# S7CAS-PLEIADES-CARTE-MERE_P07_FPGA_3.net
KiCad netlist of a schematic drawn in Altium Designer
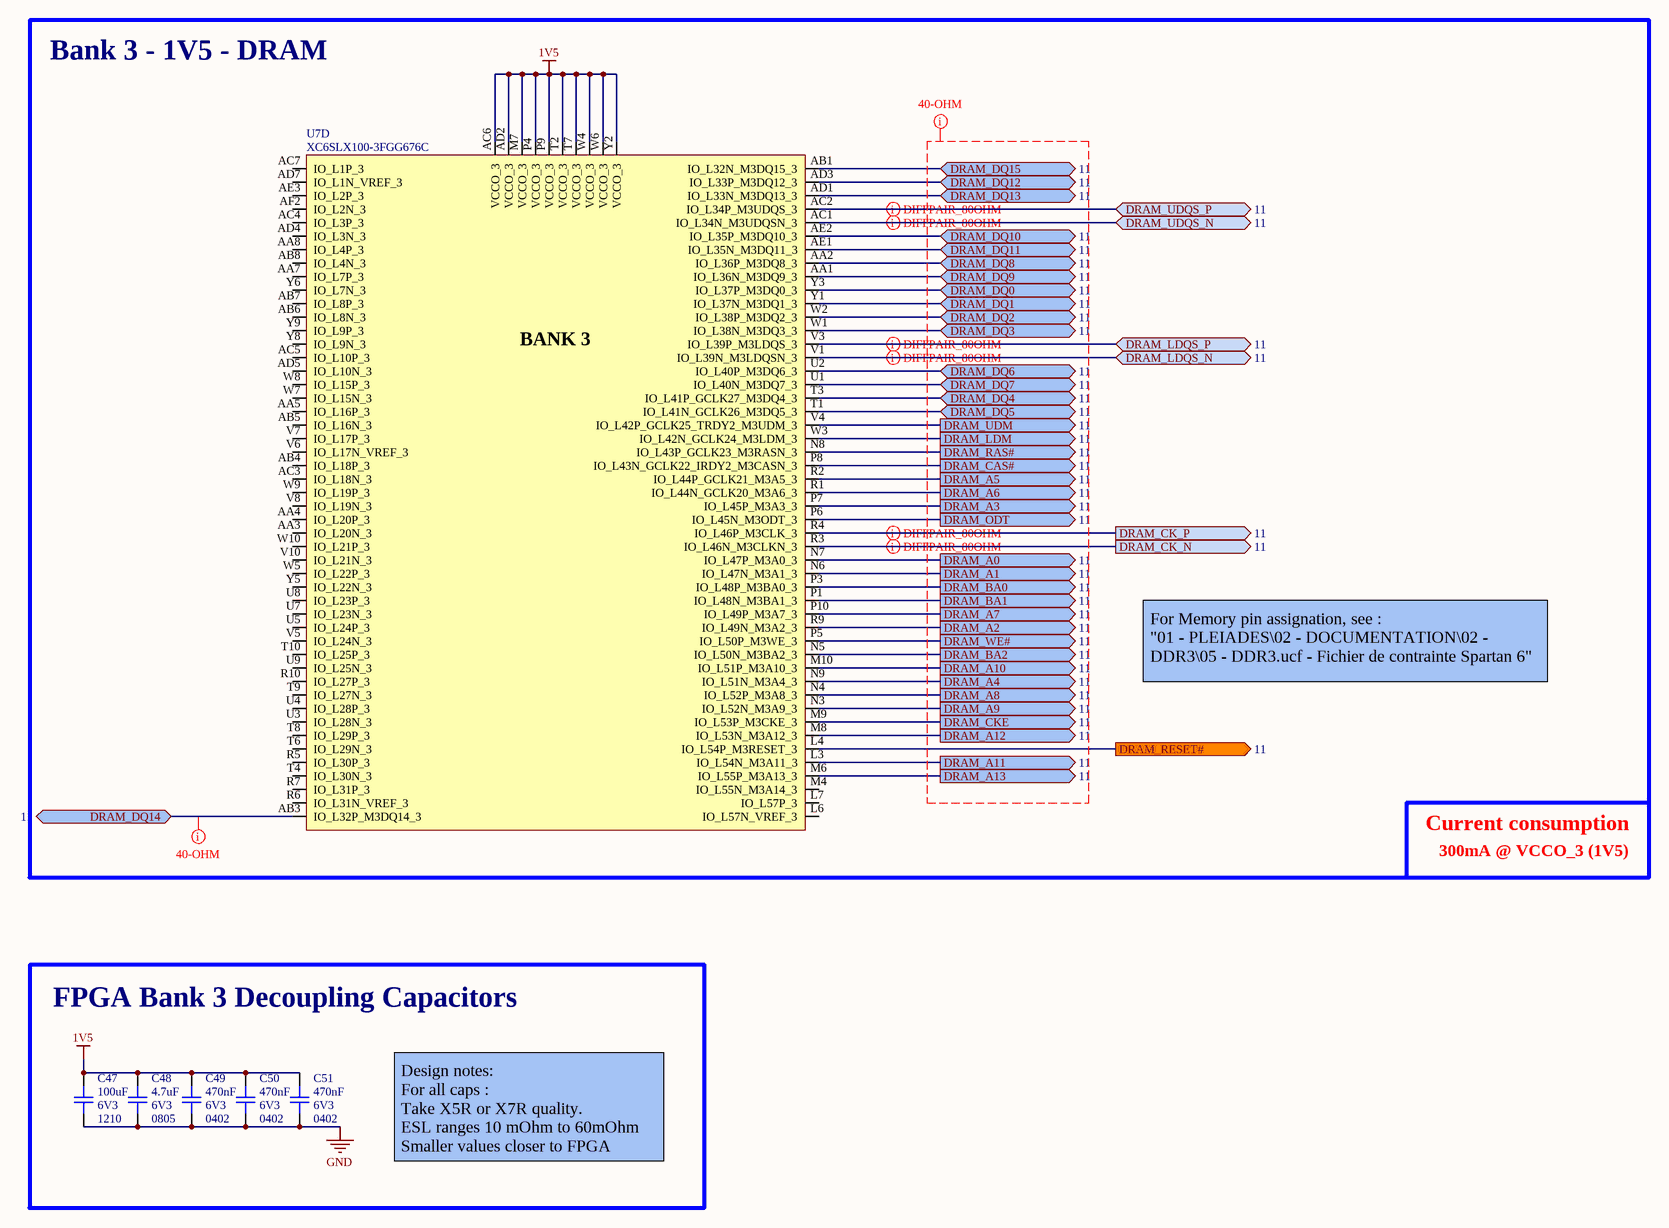
[diagram p0: S7CAS-PLEIADES-CARTE-MERE_P07_FPGA_3.SchDoc]

(export (version "E")
  (design (tool "Eeschema 10.0.6"))
  (components
    (comp (ref "C47")
      (value "100uF")
      (footprint "CAP_1210")
      (description "CAP - 1210")
      (fields
        (field (name "VOLTAGE") "6V3")
        (field (name "PACKAGE") "1210")
        (field (name "CREATEDBY") "Jonathan Bouchard")
      )
      (libsource (lib "S7CAS_LIB2021") (part "CAP - 1210"))
    )
    (comp (ref "C48")
      (value "4.7uF")
      (footprint "CAP_0805")
      (description "CAP - 0805")
      (fields
        (field (name "VOLTAGE") "6V3")
        (field (name "PACKAGE") "0805")
        (field (name "CREATEDBY") "Jonathan Bouchard")
      )
      (libsource (lib "S7CAS_LIB2021") (part "CAP - 0805"))
    )
    (comp (ref "C49")
      (value "470nF")
      (footprint "CAP_0402")
      (description "CAP - 0402")
      (fields
        (field (name "VOLTAGE") "6V3")
        (field (name "PACKAGE") "0402")
        (field (name "CREATEDBY") "Jonathan Bouchard")
      )
      (libsource (lib "S7CAS_LIB2021") (part "CAP - 0402"))
    )
    (comp (ref "C50")
      (value "470nF")
      (footprint "CAP_0402")
      (description "CAP - 0402")
      (fields
        (field (name "VOLTAGE") "6V3")
        (field (name "PACKAGE") "0402")
        (field (name "CREATEDBY") "Jonathan Bouchard")
      )
      (libsource (lib "S7CAS_LIB2021") (part "CAP - 0402"))
    )
    (comp (ref "C51")
      (value "470nF")
      (footprint "CAP_0402")
      (description "CAP - 0402")
      (fields
        (field (name "VOLTAGE") "6V3")
        (field (name "PACKAGE") "0402")
        (field (name "CREATEDBY") "Jonathan Bouchard")
      )
      (libsource (lib "S7CAS_LIB2021") (part "CAP - 0402"))
    )
    (comp (ref "U7")
      (value "XC6SLX100-3FGG676C")
      (footprint "FPGA_XILINX_FGG676")
      (description "FPGA - XILINX SPARTAN 6 480 I/O - BGA-676")
      (fields
        (field (name "VOLTAGE") "1.14 V ~ 1.26 V")
        (field (name "MFG") "Xilinx")
        (field (name "CREATEDBY") "Jonathan Bouchard")
      )
      (libsource (lib "S7CAS_LIB2021") (part "FPGA_XC6SLX100-3FGG676C"))
    )
  )
  (nets
    (net (code "1") (name "/DRAM_A0") (class "Default")
      (node (ref "U7") (pin "N7") (pinfunction "IO_L47P_M3A0_3_N7") (pintype "passive"))
    )
    (net (code "2") (name "/DRAM_A1") (class "Default")
      (node (ref "U7") (pin "N6") (pinfunction "IO_L47N_M3A1_3_N6") (pintype "passive"))
    )
    (net (code "3") (name "/DRAM_A2") (class "Default")
      (node (ref "U7") (pin "R9") (pinfunction "IO_L49N_M3A2_3_R9") (pintype "passive"))
    )
    (net (code "4") (name "/DRAM_A3") (class "Default")
      (node (ref "U7") (pin "P7") (pinfunction "IO_L45P_M3A3_3_P7") (pintype "passive"))
    )
    (net (code "5") (name "/DRAM_A4") (class "Default")
      (node (ref "U7") (pin "N9") (pinfunction "IO_L51N_M3A4_3_N9") (pintype "passive"))
    )
    (net (code "6") (name "/DRAM_A5") (class "Default")
      (node (ref "U7") (pin "R2") (pinfunction "IO_L44P_GCLK21_M3A5_3_R2") (pintype "passive"))
    )
    (net (code "7") (name "/DRAM_A6") (class "Default")
      (node (ref "U7") (pin "R1") (pinfunction "IO_L44N_GCLK20_M3A6_3_R1") (pintype "passive"))
    )
    (net (code "8") (name "/DRAM_A7") (class "Default")
      (node (ref "U7") (pin "P10") (pinfunction "IO_L49P_M3A7_3_P10") (pintype "passive"))
    )
    (net (code "9") (name "/DRAM_A8") (class "Default")
      (node (ref "U7") (pin "N4") (pinfunction "IO_L52P_M3A8_3_N4") (pintype "passive"))
    )
    (net (code "10") (name "/DRAM_A9") (class "Default")
      (node (ref "U7") (pin "N3") (pinfunction "IO_L52N_M3A9_3_N3") (pintype "passive"))
    )
    (net (code "11") (name "/DRAM_A10") (class "Default")
      (node (ref "U7") (pin "M10") (pinfunction "IO_L51P_M3A10_3_M10") (pintype "passive"))
    )
    (net (code "12") (name "/DRAM_A11") (class "Default")
      (node (ref "U7") (pin "L3") (pinfunction "IO_L54N_M3A11_3_L3") (pintype "passive"))
    )
    (net (code "13") (name "/DRAM_A12") (class "Default")
      (node (ref "U7") (pin "M8") (pinfunction "IO_L53N_M3A12_3_M8") (pintype "passive"))
    )
    (net (code "14") (name "/DRAM_A13") (class "Default")
      (node (ref "U7") (pin "M6") (pinfunction "IO_L55P_M3A13_3_M6") (pintype "passive"))
    )
    (net (code "15") (name "/DRAM_BA0") (class "Default")
      (node (ref "U7") (pin "P3") (pinfunction "IO_L48P_M3BA0_3_P3") (pintype "passive"))
    )
    (net (code "16") (name "/DRAM_BA1") (class "Default")
      (node (ref "U7") (pin "P1") (pinfunction "IO_L48N_M3BA1_3_P1") (pintype "passive"))
    )
    (net (code "17") (name "/DRAM_BA2") (class "Default")
      (node (ref "U7") (pin "N5") (pinfunction "IO_L50N_M3BA2_3_N5") (pintype "passive"))
    )
    (net (code "18") (name "/DRAM_CAS#") (class "Default")
      (node (ref "U7") (pin "P8") (pinfunction "IO_L43N_GCLK22_IRDY2_M3CASN_3_P8") (pintype "passive"))
    )
    (net (code "19") (name "/DRAM_CKE") (class "Default")
      (node (ref "U7") (pin "M9") (pinfunction "IO_L53P_M3CKE_3_M9") (pintype "passive"))
    )
    (net (code "20") (name "/DRAM_CK_N") (class "Default")
      (node (ref "U7") (pin "R3") (pinfunction "IO_L46N_M3CLKN_3_R3") (pintype "passive"))
    )
    (net (code "21") (name "/DRAM_CK_P") (class "Default")
      (node (ref "U7") (pin "R4") (pinfunction "IO_L46P_M3CLK_3_R4") (pintype "passive"))
    )
    (net (code "22") (name "/DRAM_DQ0") (class "Default")
      (node (ref "U7") (pin "Y3") (pinfunction "IO_L37P_M3DQ0_3_Y3") (pintype "passive"))
    )
    (net (code "23") (name "/DRAM_DQ1") (class "Default")
      (node (ref "U7") (pin "Y1") (pinfunction "IO_L37N_M3DQ1_3_Y1") (pintype "passive"))
    )
    (net (code "24") (name "/DRAM_DQ2") (class "Default")
      (node (ref "U7") (pin "W2") (pinfunction "IO_L38P_M3DQ2_3_W2") (pintype "passive"))
    )
    (net (code "25") (name "/DRAM_DQ3") (class "Default")
      (node (ref "U7") (pin "W1") (pinfunction "IO_L38N_M3DQ3_3_W1") (pintype "passive"))
    )
    (net (code "26") (name "/DRAM_DQ4") (class "Default")
      (node (ref "U7") (pin "T3") (pinfunction "IO_L41P_GCLK27_M3DQ4_3_T3") (pintype "passive"))
    )
    (net (code "27") (name "/DRAM_DQ5") (class "Default")
      (node (ref "U7") (pin "T1") (pinfunction "IO_L41N_GCLK26_M3DQ5_3_T1") (pintype "passive"))
    )
    (net (code "28") (name "/DRAM_DQ6") (class "Default")
      (node (ref "U7") (pin "U2") (pinfunction "IO_L40P_M3DQ6_3_U2") (pintype "passive"))
    )
    (net (code "29") (name "/DRAM_DQ7") (class "Default")
      (node (ref "U7") (pin "U1") (pinfunction "IO_L40N_M3DQ7_3_U1") (pintype "passive"))
    )
    (net (code "30") (name "/DRAM_DQ8") (class "Default")
      (node (ref "U7") (pin "AA2") (pinfunction "IO_L36P_M3DQ8_3_AA2") (pintype "passive"))
    )
    (net (code "31") (name "/DRAM_DQ9") (class "Default")
      (node (ref "U7") (pin "AA1") (pinfunction "IO_L36N_M3DQ9_3_AA1") (pintype "passive"))
    )
    (net (code "32") (name "/DRAM_DQ10") (class "Default")
      (node (ref "U7") (pin "AE2") (pinfunction "IO_L35P_M3DQ10_3_AE2") (pintype "passive"))
    )
    (net (code "33") (name "/DRAM_DQ11") (class "Default")
      (node (ref "U7") (pin "AE1") (pinfunction "IO_L35N_M3DQ11_3_AE1") (pintype "passive"))
    )
    (net (code "34") (name "/DRAM_DQ12") (class "Default")
      (node (ref "U7") (pin "AD3") (pinfunction "IO_L33P_M3DQ12_3_AD3") (pintype "passive"))
    )
    (net (code "35") (name "/DRAM_DQ13") (class "Default")
      (node (ref "U7") (pin "AD1") (pinfunction "IO_L33N_M3DQ13_3_AD1") (pintype "passive"))
    )
    (net (code "36") (name "/DRAM_DQ14") (class "Default")
      (node (ref "U7") (pin "AB3") (pinfunction "IO_L32P_M3DQ14_3_AB3") (pintype "passive"))
    )
    (net (code "37") (name "/DRAM_DQ15") (class "Default")
      (node (ref "U7") (pin "AB1") (pinfunction "IO_L32N_M3DQ15_3_AB1") (pintype "passive"))
    )
    (net (code "38") (name "/DRAM_LDM") (class "Default")
      (node (ref "U7") (pin "W3") (pinfunction "IO_L42N_GCLK24_M3LDM_3_W3") (pintype "passive"))
    )
    (net (code "39") (name "/DRAM_LDQS_N") (class "Default")
      (node (ref "U7") (pin "V1") (pinfunction "IO_L39N_M3LDQSN_3_V1") (pintype "passive"))
    )
    (net (code "40") (name "/DRAM_LDQS_P") (class "Default")
      (node (ref "U7") (pin "V3") (pinfunction "IO_L39P_M3LDQS_3_V3") (pintype "passive"))
    )
    (net (code "41") (name "/DRAM_ODT") (class "Default")
      (node (ref "U7") (pin "P6") (pinfunction "IO_L45N_M3ODT_3_P6") (pintype "passive"))
    )
    (net (code "42") (name "/DRAM_RAS#") (class "Default")
      (node (ref "U7") (pin "N8") (pinfunction "IO_L43P_GCLK23_M3RASN_3_N8") (pintype "passive"))
    )
    (net (code "43") (name "/DRAM_RESET#") (class "Default")
      (node (ref "U7") (pin "L4") (pinfunction "IO_L54P_M3RESET_3_L4") (pintype "passive"))
    )
    (net (code "44") (name "/DRAM_UDM") (class "Default")
      (node (ref "U7") (pin "V4") (pinfunction "IO_L42P_GCLK25_TRDY2_M3UDM_3_V4") (pintype "passive"))
    )
    (net (code "45") (name "/DRAM_UDQS_N") (class "Default")
      (node (ref "U7") (pin "AC1") (pinfunction "IO_L34N_M3UDQSN_3_AC1") (pintype "passive"))
    )
    (net (code "46") (name "/DRAM_UDQS_P") (class "Default")
      (node (ref "U7") (pin "AC2") (pinfunction "IO_L34P_M3UDQS_3_AC2") (pintype "passive"))
    )
    (net (code "47") (name "/DRAM_WE#") (class "Default")
      (node (ref "U7") (pin "P5") (pinfunction "IO_L50P_M3WE_3_P5") (pintype "passive"))
    )
    (net (code "48") (name "1V5") (class "Default")
      (node (ref "C47") (pin "2") (pinfunction "2_2") (pintype "passive"))
      (node (ref "C48") (pin "2") (pinfunction "2_2") (pintype "passive"))
      (node (ref "C49") (pin "2") (pinfunction "2_2") (pintype "passive"))
      (node (ref "C50") (pin "2") (pinfunction "2_2") (pintype "passive"))
      (node (ref "C51") (pin "2") (pinfunction "2_2") (pintype "passive"))
      (node (ref "U7") (pin "AC6") (pinfunction "VCCO_3_AC6") (pintype "passive"))
      (node (ref "U7") (pin "AD2") (pinfunction "VCCO_3_AD2") (pintype "passive"))
      (node (ref "U7") (pin "M7") (pinfunction "VCCO_3_M7") (pintype "passive"))
      (node (ref "U7") (pin "P4") (pinfunction "VCCO_3_P4") (pintype "passive"))
      (node (ref "U7") (pin "P9") (pinfunction "VCCO_3_P9") (pintype "passive"))
      (node (ref "U7") (pin "T2") (pinfunction "VCCO_3_T2") (pintype "passive"))
      (node (ref "U7") (pin "T7") (pinfunction "VCCO_3_T7") (pintype "passive"))
      (node (ref "U7") (pin "W4") (pinfunction "VCCO_3_W4") (pintype "passive"))
      (node (ref "U7") (pin "W6") (pinfunction "VCCO_3_W6") (pintype "passive"))
      (node (ref "U7") (pin "Y2") (pinfunction "VCCO_3_Y2") (pintype "passive"))
    )
    (net (code "49") (name "GND") (class "Default")
      (node (ref "C47") (pin "1") (pinfunction "1_1") (pintype "passive"))
      (node (ref "C48") (pin "1") (pinfunction "1_1") (pintype "passive"))
      (node (ref "C49") (pin "1") (pinfunction "1_1") (pintype "passive"))
      (node (ref "C50") (pin "1") (pinfunction "1_1") (pintype "passive"))
      (node (ref "C51") (pin "1") (pinfunction "1_1") (pintype "passive"))
    )
    (net (code "50") (name "unconnected-(U7D-IO_L1N_VREF_3-PadAD7)") (class "Default")
      (node (ref "U7") (pin "AD7") (pinfunction "IO_L1N_VREF_3_AD7") (pintype "passive"))
    )
    (net (code "51") (name "unconnected-(U7D-IO_L1P_3-PadAC7)") (class "Default")
      (node (ref "U7") (pin "AC7") (pinfunction "IO_L1P_3_AC7") (pintype "passive"))
    )
    (net (code "52") (name "unconnected-(U7D-IO_L2N_3-PadAF2)") (class "Default")
      (node (ref "U7") (pin "AF2") (pinfunction "IO_L2N_3_AF2") (pintype "passive"))
    )
    (net (code "53") (name "unconnected-(U7D-IO_L2P_3-PadAE3)") (class "Default")
      (node (ref "U7") (pin "AE3") (pinfunction "IO_L2P_3_AE3") (pintype "passive"))
    )
    (net (code "54") (name "unconnected-(U7D-IO_L3N_3-PadAD4)") (class "Default")
      (node (ref "U7") (pin "AD4") (pinfunction "IO_L3N_3_AD4") (pintype "passive"))
    )
    (net (code "55") (name "unconnected-(U7D-IO_L3P_3-PadAC4)") (class "Default")
      (node (ref "U7") (pin "AC4") (pinfunction "IO_L3P_3_AC4") (pintype "passive"))
    )
    (net (code "56") (name "unconnected-(U7D-IO_L4N_3-PadAB8)") (class "Default")
      (node (ref "U7") (pin "AB8") (pinfunction "IO_L4N_3_AB8") (pintype "passive"))
    )
    (net (code "57") (name "unconnected-(U7D-IO_L4P_3-PadAA8)") (class "Default")
      (node (ref "U7") (pin "AA8") (pinfunction "IO_L4P_3_AA8") (pintype "passive"))
    )
    (net (code "58") (name "unconnected-(U7D-IO_L7N_3-PadY6)") (class "Default")
      (node (ref "U7") (pin "Y6") (pinfunction "IO_L7N_3_Y6") (pintype "passive"))
    )
    (net (code "59") (name "unconnected-(U7D-IO_L7P_3-PadAA7)") (class "Default")
      (node (ref "U7") (pin "AA7") (pinfunction "IO_L7P_3_AA7") (pintype "passive"))
    )
    (net (code "60") (name "unconnected-(U7D-IO_L8N_3-PadAB6)") (class "Default")
      (node (ref "U7") (pin "AB6") (pinfunction "IO_L8N_3_AB6") (pintype "passive"))
    )
    (net (code "61") (name "unconnected-(U7D-IO_L8P_3-PadAB7)") (class "Default")
      (node (ref "U7") (pin "AB7") (pinfunction "IO_L8P_3_AB7") (pintype "passive"))
    )
    (net (code "62") (name "unconnected-(U7D-IO_L9N_3-PadY8)") (class "Default")
      (node (ref "U7") (pin "Y8") (pinfunction "IO_L9N_3_Y8") (pintype "passive"))
    )
    (net (code "63") (name "unconnected-(U7D-IO_L9P_3-PadY9)") (class "Default")
      (node (ref "U7") (pin "Y9") (pinfunction "IO_L9P_3_Y9") (pintype "passive"))
    )
    (net (code "64") (name "unconnected-(U7D-IO_L10N_3-PadAD5)") (class "Default")
      (node (ref "U7") (pin "AD5") (pinfunction "IO_L10N_3_AD5") (pintype "passive"))
    )
    (net (code "65") (name "unconnected-(U7D-IO_L10P_3-PadAC5)") (class "Default")
      (node (ref "U7") (pin "AC5") (pinfunction "IO_L10P_3_AC5") (pintype "passive"))
    )
    (net (code "66") (name "unconnected-(U7D-IO_L15N_3-PadW7)") (class "Default")
      (node (ref "U7") (pin "W7") (pinfunction "IO_L15N_3_W7") (pintype "passive"))
    )
    (net (code "67") (name "unconnected-(U7D-IO_L15P_3-PadW8)") (class "Default")
      (node (ref "U7") (pin "W8") (pinfunction "IO_L15P_3_W8") (pintype "passive"))
    )
    (net (code "68") (name "unconnected-(U7D-IO_L16N_3-PadAB5)") (class "Default")
      (node (ref "U7") (pin "AB5") (pinfunction "IO_L16N_3_AB5") (pintype "passive"))
    )
    (net (code "69") (name "unconnected-(U7D-IO_L16P_3-PadAA5)") (class "Default")
      (node (ref "U7") (pin "AA5") (pinfunction "IO_L16P_3_AA5") (pintype "passive"))
    )
    (net (code "70") (name "unconnected-(U7D-IO_L17N_VREF_3-PadV6)") (class "Default")
      (node (ref "U7") (pin "V6") (pinfunction "IO_L17N_VREF_3_V6") (pintype "passive"))
    )
    (net (code "71") (name "unconnected-(U7D-IO_L17P_3-PadV7)") (class "Default")
      (node (ref "U7") (pin "V7") (pinfunction "IO_L17P_3_V7") (pintype "passive"))
    )
    (net (code "72") (name "unconnected-(U7D-IO_L18N_3-PadAC3)") (class "Default")
      (node (ref "U7") (pin "AC3") (pinfunction "IO_L18N_3_AC3") (pintype "passive"))
    )
    (net (code "73") (name "unconnected-(U7D-IO_L18P_3-PadAB4)") (class "Default")
      (node (ref "U7") (pin "AB4") (pinfunction "IO_L18P_3_AB4") (pintype "passive"))
    )
    (net (code "74") (name "unconnected-(U7D-IO_L19N_3-PadV8)") (class "Default")
      (node (ref "U7") (pin "V8") (pinfunction "IO_L19N_3_V8") (pintype "passive"))
    )
    (net (code "75") (name "unconnected-(U7D-IO_L19P_3-PadW9)") (class "Default")
      (node (ref "U7") (pin "W9") (pinfunction "IO_L19P_3_W9") (pintype "passive"))
    )
    (net (code "76") (name "unconnected-(U7D-IO_L20N_3-PadAA3)") (class "Default")
      (node (ref "U7") (pin "AA3") (pinfunction "IO_L20N_3_AA3") (pintype "passive"))
    )
    (net (code "77") (name "unconnected-(U7D-IO_L20P_3-PadAA4)") (class "Default")
      (node (ref "U7") (pin "AA4") (pinfunction "IO_L20P_3_AA4") (pintype "passive"))
    )
    (net (code "78") (name "unconnected-(U7D-IO_L21N_3-PadV10)") (class "Default")
      (node (ref "U7") (pin "V10") (pinfunction "IO_L21N_3_V10") (pintype "passive"))
    )
    (net (code "79") (name "unconnected-(U7D-IO_L21P_3-PadW10)") (class "Default")
      (node (ref "U7") (pin "W10") (pinfunction "IO_L21P_3_W10") (pintype "passive"))
    )
    (net (code "80") (name "unconnected-(U7D-IO_L22N_3-PadY5)") (class "Default")
      (node (ref "U7") (pin "Y5") (pinfunction "IO_L22N_3_Y5") (pintype "passive"))
    )
    (net (code "81") (name "unconnected-(U7D-IO_L22P_3-PadW5)") (class "Default")
      (node (ref "U7") (pin "W5") (pinfunction "IO_L22P_3_W5") (pintype "passive"))
    )
    (net (code "82") (name "unconnected-(U7D-IO_L23N_3-PadU7)") (class "Default")
      (node (ref "U7") (pin "U7") (pinfunction "IO_L23N_3_U7") (pintype "passive"))
    )
    (net (code "83") (name "unconnected-(U7D-IO_L23P_3-PadU8)") (class "Default")
      (node (ref "U7") (pin "U8") (pinfunction "IO_L23P_3_U8") (pintype "passive"))
    )
    (net (code "84") (name "unconnected-(U7D-IO_L24N_3-PadV5)") (class "Default")
      (node (ref "U7") (pin "V5") (pinfunction "IO_L24N_3_V5") (pintype "passive"))
    )
    (net (code "85") (name "unconnected-(U7D-IO_L24P_3-PadU5)") (class "Default")
      (node (ref "U7") (pin "U5") (pinfunction "IO_L24P_3_U5") (pintype "passive"))
    )
    (net (code "86") (name "unconnected-(U7D-IO_L25N_3-PadU9)") (class "Default")
      (node (ref "U7") (pin "U9") (pinfunction "IO_L25N_3_U9") (pintype "passive"))
    )
    (net (code "87") (name "unconnected-(U7D-IO_L25P_3-PadT10)") (class "Default")
      (node (ref "U7") (pin "T10") (pinfunction "IO_L25P_3_T10") (pintype "passive"))
    )
    (net (code "88") (name "unconnected-(U7D-IO_L27N_3-PadT9)") (class "Default")
      (node (ref "U7") (pin "T9") (pinfunction "IO_L27N_3_T9") (pintype "passive"))
    )
    (net (code "89") (name "unconnected-(U7D-IO_L27P_3-PadR10)") (class "Default")
      (node (ref "U7") (pin "R10") (pinfunction "IO_L27P_3_R10") (pintype "passive"))
    )
    (net (code "90") (name "unconnected-(U7D-IO_L28N_3-PadU3)") (class "Default")
      (node (ref "U7") (pin "U3") (pinfunction "IO_L28N_3_U3") (pintype "passive"))
    )
    (net (code "91") (name "unconnected-(U7D-IO_L28P_3-PadU4)") (class "Default")
      (node (ref "U7") (pin "U4") (pinfunction "IO_L28P_3_U4") (pintype "passive"))
    )
    (net (code "92") (name "unconnected-(U7D-IO_L29N_3-PadT6)") (class "Default")
      (node (ref "U7") (pin "T6") (pinfunction "IO_L29N_3_T6") (pintype "passive"))
    )
    (net (code "93") (name "unconnected-(U7D-IO_L29P_3-PadT8)") (class "Default")
      (node (ref "U7") (pin "T8") (pinfunction "IO_L29P_3_T8") (pintype "passive"))
    )
    (net (code "94") (name "unconnected-(U7D-IO_L30N_3-PadT4)") (class "Default")
      (node (ref "U7") (pin "T4") (pinfunction "IO_L30N_3_T4") (pintype "passive"))
    )
    (net (code "95") (name "unconnected-(U7D-IO_L30P_3-PadR5)") (class "Default")
      (node (ref "U7") (pin "R5") (pinfunction "IO_L30P_3_R5") (pintype "passive"))
    )
    (net (code "96") (name "unconnected-(U7D-IO_L31N_VREF_3-PadR6)") (class "Default")
      (node (ref "U7") (pin "R6") (pinfunction "IO_L31N_VREF_3_R6") (pintype "passive"))
    )
    (net (code "97") (name "unconnected-(U7D-IO_L31P_3-PadR7)") (class "Default")
      (node (ref "U7") (pin "R7") (pinfunction "IO_L31P_3_R7") (pintype "passive"))
    )
    (net (code "98") (name "unconnected-(U7D-IO_L55N_M3A14_3-PadM4)") (class "Default")
      (node (ref "U7") (pin "M4") (pinfunction "IO_L55N_M3A14_3_M4") (pintype "passive"))
    )
    (net (code "99") (name "unconnected-(U7D-IO_L57N_VREF_3-PadL6)") (class "Default")
      (node (ref "U7") (pin "L6") (pinfunction "IO_L57N_VREF_3_L6") (pintype "passive"))
    )
    (net (code "100") (name "unconnected-(U7D-IO_L57P_3-PadL7)") (class "Default")
      (node (ref "U7") (pin "L7") (pinfunction "IO_L57P_3_L7") (pintype "passive"))
    )
  )
)
